# CONNECTORS.net
KiCad netlist of a schematic drawn in Altium Designer
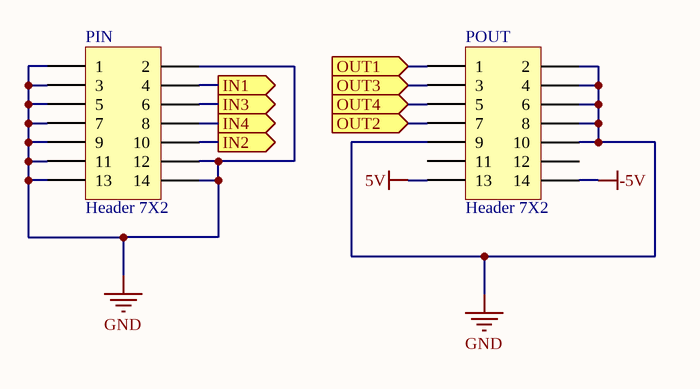
[diagram p0: CONNECTORS.SchDoc]

(export (version "E")
  (design (tool "Eeschema 10.0.6"))
  (components
    (comp (ref "PIN")
      (value "Header 7X2")
      (footprint "CLP-107-02-L-DH-TR")
      (description "Header, 7-Pin, Dual row")
      (fields (field (name "PUBLISHER") "Altium Limited"))
      (libsource (lib "Miscellaneous Connectors") (part "Header 7X2"))
    )
    (comp (ref "POUT")
      (value "Header 7X2")
      (footprint "FTSH-107-01-L-DH")
      (description "Header, 7-Pin, Dual row")
      (fields (field (name "PUBLISHER") "Altium Limited"))
      (libsource (lib "Miscellaneous Connectors") (part "Header 7X2"))
    )
  )
  (nets
    (net (code "1") (name "-5V") (class "Default")
      (node (ref "POUT") (pin "14") (pinfunction "14_14") (pintype "passive"))
    )
    (net (code "2") (name "/IN1") (class "Default")
      (node (ref "PIN") (pin "4") (pinfunction "4_4") (pintype "passive"))
    )
    (net (code "3") (name "/IN2") (class "Default")
      (node (ref "PIN") (pin "10") (pinfunction "10_10") (pintype "passive"))
    )
    (net (code "4") (name "/IN3") (class "Default")
      (node (ref "PIN") (pin "6") (pinfunction "6_6") (pintype "passive"))
    )
    (net (code "5") (name "/IN4") (class "Default")
      (node (ref "PIN") (pin "8") (pinfunction "8_8") (pintype "passive"))
    )
    (net (code "6") (name "/OUT1") (class "Default")
      (node (ref "POUT") (pin "1") (pinfunction "1_1") (pintype "passive"))
    )
    (net (code "7") (name "/OUT2") (class "Default")
      (node (ref "POUT") (pin "7") (pinfunction "7_7") (pintype "passive"))
    )
    (net (code "8") (name "/OUT3") (class "Default")
      (node (ref "POUT") (pin "3") (pinfunction "3_3") (pintype "passive"))
    )
    (net (code "9") (name "/OUT4") (class "Default")
      (node (ref "POUT") (pin "5") (pinfunction "5_5") (pintype "passive"))
    )
    (net (code "10") (name "5V") (class "Default")
      (node (ref "POUT") (pin "13") (pinfunction "13_13") (pintype "passive"))
    )
    (net (code "11") (name "GND") (class "Default")
      (node (ref "PIN") (pin "1") (pinfunction "1_1") (pintype "passive"))
      (node (ref "PIN") (pin "11") (pinfunction "11_11") (pintype "passive"))
      (node (ref "PIN") (pin "12") (pinfunction "12_12") (pintype "passive"))
      (node (ref "PIN") (pin "13") (pinfunction "13_13") (pintype "passive"))
      (node (ref "PIN") (pin "14") (pinfunction "14_14") (pintype "passive"))
      (node (ref "PIN") (pin "2") (pinfunction "2_2") (pintype "passive"))
      (node (ref "PIN") (pin "3") (pinfunction "3_3") (pintype "passive"))
      (node (ref "PIN") (pin "5") (pinfunction "5_5") (pintype "passive"))
      (node (ref "PIN") (pin "7") (pinfunction "7_7") (pintype "passive"))
      (node (ref "PIN") (pin "9") (pinfunction "9_9") (pintype "passive"))
      (node (ref "POUT") (pin "10") (pinfunction "10_10") (pintype "passive"))
      (node (ref "POUT") (pin "2") (pinfunction "2_2") (pintype "passive"))
      (node (ref "POUT") (pin "4") (pinfunction "4_4") (pintype "passive"))
      (node (ref "POUT") (pin "6") (pinfunction "6_6") (pintype "passive"))
      (node (ref "POUT") (pin "8") (pinfunction "8_8") (pintype "passive"))
      (node (ref "POUT") (pin "9") (pinfunction "9_9") (pintype "passive"))
    )
    (net (code "12") (name "unconnected-(POUT-Pad11)") (class "Default")
      (node (ref "POUT") (pin "11") (pinfunction "11_11") (pintype "passive"))
    )
    (net (code "13") (name "unconnected-(POUT-Pad12)") (class "Default")
      (node (ref "POUT") (pin "12") (pinfunction "12_12") (pintype "passive"))
    )
  )
)
